# Sch_Dr_Baro.net
KiCad netlist of a schematic drawn in Altium Designer
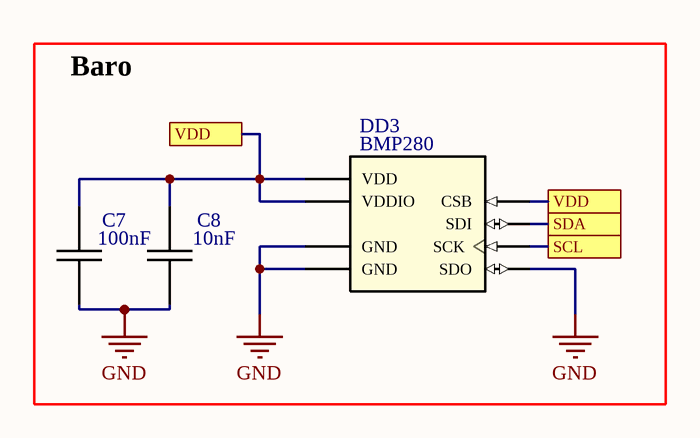
[diagram p0: Sch_Dr_Baro.SchDoc]

(export (version "E")
  (design (tool "Eeschema 10.0.6"))
  (components
    (comp (ref "C7")
      (value "100nF")
      (footprint "Cap_0603")
      (description "CC0603JRX7R8BB104")
      (libsource (lib "Dr_lib") (part "Cap_"))
    )
    (comp (ref "C8")
      (value "10nF")
      (footprint "Cap_0603")
      (description "CC0603JRNPO9BN103")
      (libsource (lib "Dr_lib") (part "Cap_"))
    )
    (comp (ref "DD3")
      (value "BMP280")
      (footprint "8-pin metal-lid LGA 2.0*2.5*0.95")
      (description "BMP280 Absolute Barometric Pressure Sensor for Battery Powered Devices 2 x 2.5mm")
      (libsource (lib "Dr_lib") (part "BMP280"))
    )
  )
  (nets
    (net (code "1") (name "/SCL") (class "Default")
      (node (ref "DD3") (pin "4") (pinfunction "SCK_4") (pintype "input"))
    )
    (net (code "2") (name "/SDA") (class "Default")
      (node (ref "DD3") (pin "3") (pinfunction "SDI_3") (pintype "bidirectional"))
    )
    (net (code "3") (name "/VDD") (class "Default")
      (node (ref "C7") (pin "2") (pinfunction "2_2") (pintype "passive"))
      (node (ref "C8") (pin "2") (pinfunction "2_2") (pintype "passive"))
      (node (ref "DD3") (pin "2") (pinfunction "CSB_2") (pintype "input"))
      (node (ref "DD3") (pin "6") (pinfunction "VDDIO_6") (pintype "passive"))
      (node (ref "DD3") (pin "8") (pinfunction "VDD_8") (pintype "passive"))
    )
    (net (code "4") (name "GND") (class "Default")
      (node (ref "C7") (pin "1") (pinfunction "1_1") (pintype "passive"))
      (node (ref "C8") (pin "1") (pinfunction "1_1") (pintype "passive"))
      (node (ref "DD3") (pin "1") (pinfunction "GND_1") (pintype "passive"))
      (node (ref "DD3") (pin "5") (pinfunction "SDO_5") (pintype "bidirectional"))
      (node (ref "DD3") (pin "7") (pinfunction "GND_7") (pintype "passive"))
    )
  )
)
